# blackfin_d_codec.net
KiCad netlist of a schematic drawn in Altium Designer
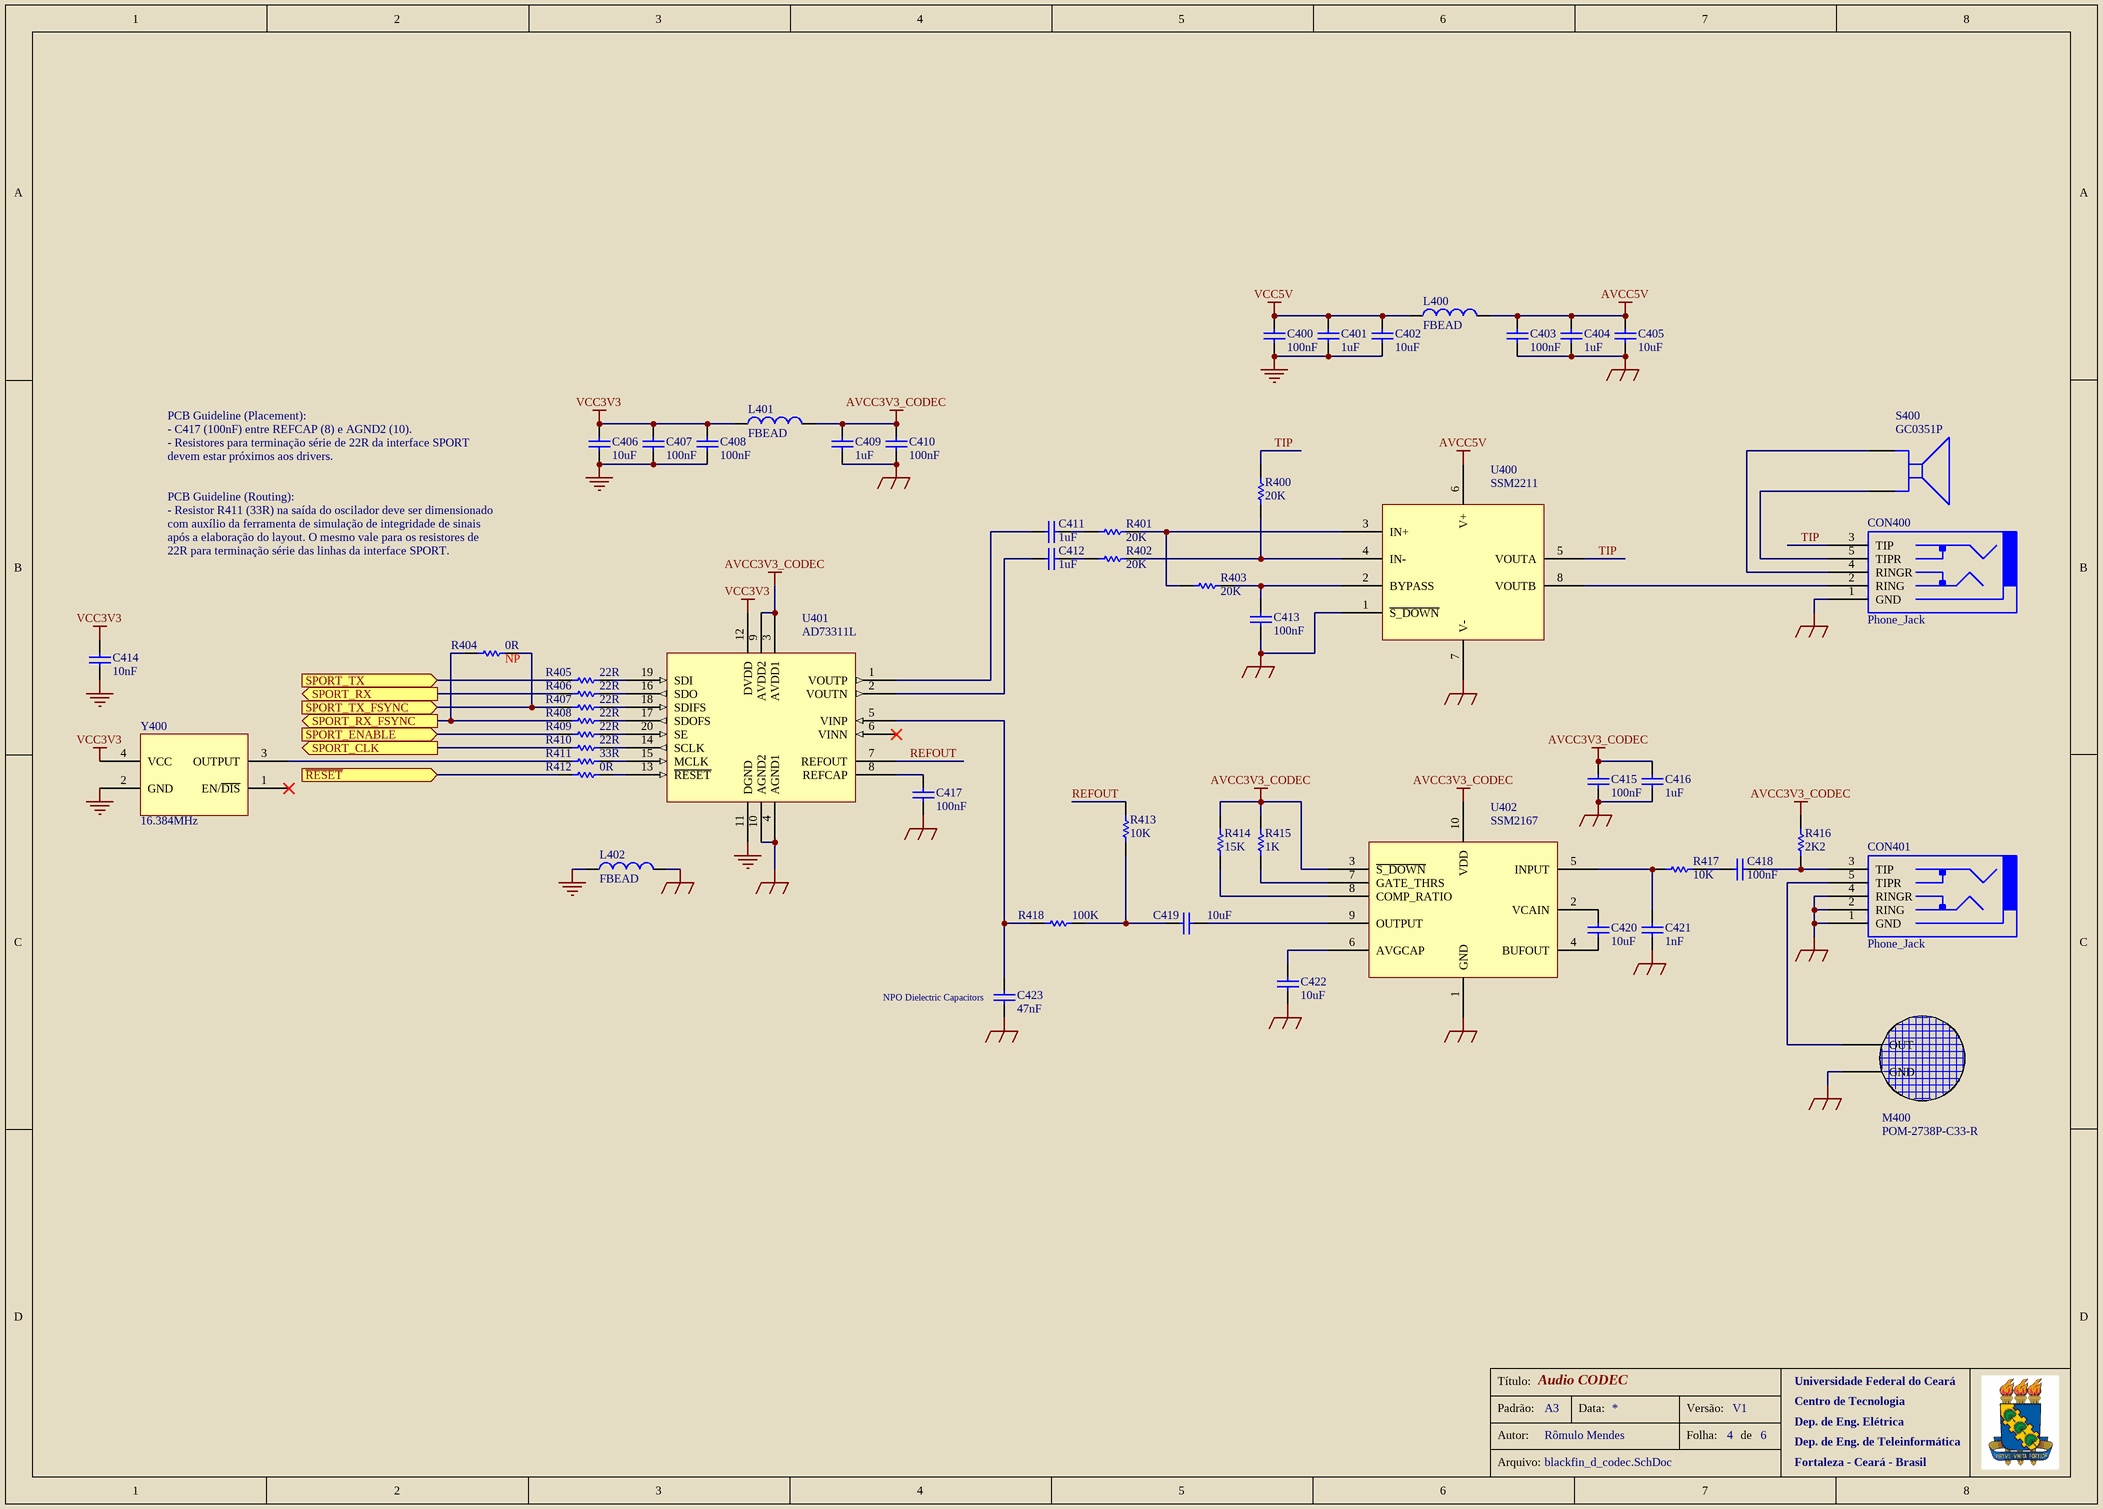
[diagram p0: blackfin_d_codec.SchDoc]

(export (version "E")
  (design (tool "Eeschema 10.0.6"))
  (components
    (comp (ref "C400")
      (value "100nF")
      (footprint "blackfin_pcblib:C_0603")
      (fields
        (field (name "EVENDORPART#") "81-GRM188R71E104KA01")
        (field (name "MANUFACTURER") "Murata")
        (field (name "PART#") "GRM188R71E104KA01J")
      )
      (libsource (lib "blackfin_schlib") (part "Capacitor"))
    )
    (comp (ref "C401")
      (value "1uF")
      (footprint "blackfin_pcblib:C_0603")
      (fields
        (field (name "EVENDORPART#") "81-GRM188F51E105ZA12")
        (field (name "MANUFACTURER") "Murata")
        (field (name "PART#") "GRM188F51E105ZA12D")
      )
      (libsource (lib "blackfin_schlib") (part "Capacitor"))
    )
    (comp (ref "C402")
      (value "10uF")
      (footprint "blackfin_pcblib:C_0805")
      (fields
        (field (name "EVENDORPART#") "810-C2012Y5V1C106Z")
        (field (name "MANUFACTURER") "TDK")
        (field (name "PART#") "C2012Y5V1C106Z")
      )
      (libsource (lib "blackfin_schlib") (part "Capacitor"))
    )
    (comp (ref "C403")
      (value "100nF")
      (footprint "blackfin_pcblib:C_0603")
      (fields
        (field (name "EVENDORPART#") "81-GRM188R71E104KA01")
        (field (name "MANUFACTURER") "Murata")
        (field (name "PART#") "GRM188R71E104KA01J")
      )
      (libsource (lib "blackfin_schlib") (part "Capacitor"))
    )
    (comp (ref "C404")
      (value "1uF")
      (footprint "blackfin_pcblib:C_0603")
      (fields
        (field (name "EVENDORPART#") "81-GRM188F51E105ZA12")
        (field (name "MANUFACTURER") "Murata")
        (field (name "PART#") "GRM188F51E105ZA12D")
      )
      (libsource (lib "blackfin_schlib") (part "Capacitor"))
    )
    (comp (ref "C405")
      (value "10uF")
      (footprint "blackfin_pcblib:C_0805")
      (fields
        (field (name "EVENDORPART#") "810-C2012Y5V1C106Z")
        (field (name "MANUFACTURER") "TDK")
        (field (name "PART#") "C2012Y5V1C106Z")
      )
      (libsource (lib "blackfin_schlib") (part "Capacitor"))
    )
    (comp (ref "C406")
      (value "10uF")
      (footprint "blackfin_pcblib:C_0805")
      (fields
        (field (name "EVENDORPART#") "810-C2012Y5V1C106Z")
        (field (name "MANUFACTURER") "TDK")
        (field (name "PART#") "C2012Y5V1C106Z")
      )
      (libsource (lib "blackfin_schlib") (part "Capacitor"))
    )
    (comp (ref "C407")
      (value "100nF")
      (footprint "blackfin_pcblib:C_0603")
      (fields
        (field (name "EVENDORPART#") "81-GRM188R71E104KA01")
        (field (name "MANUFACTURER") "Murata")
        (field (name "PART#") "GRM188R71E104KA01J")
      )
      (libsource (lib "blackfin_schlib") (part "Capacitor"))
    )
    (comp (ref "C408")
      (value "100nF")
      (footprint "blackfin_pcblib:C_0603")
      (fields
        (field (name "EVENDORPART#") "81-GRM188R71E104KA01")
        (field (name "MANUFACTURER") "Murata")
        (field (name "PART#") "GRM188R71E104KA01J")
      )
      (libsource (lib "blackfin_schlib") (part "Capacitor"))
    )
    (comp (ref "C409")
      (value "1uF")
      (footprint "blackfin_pcblib:C_0603")
      (fields
        (field (name "EVENDORPART#") "81-GRM188F51E105ZA12")
        (field (name "MANUFACTURER") "Murata")
        (field (name "PART#") "GRM188F51E105ZA12D")
      )
      (libsource (lib "blackfin_schlib") (part "Capacitor"))
    )
    (comp (ref "C410")
      (value "100nF")
      (footprint "blackfin_pcblib:C_0603")
      (fields
        (field (name "EVENDORPART#") "81-GRM188R71E104KA01")
        (field (name "MANUFACTURER") "Murata")
        (field (name "PART#") "GRM188R71E104KA01J")
      )
      (libsource (lib "blackfin_schlib") (part "Capacitor"))
    )
    (comp (ref "C411")
      (value "1uF")
      (footprint "blackfin_pcblib:C_0603")
      (fields
        (field (name "EVENDORPART#") "81-GRM188F51E105ZA12")
        (field (name "MANUFACTURER") "Murata")
        (field (name "PART#") "GRM188F51E105ZA12D")
      )
      (libsource (lib "blackfin_schlib") (part "Capacitor"))
    )
    (comp (ref "C412")
      (value "1uF")
      (footprint "blackfin_pcblib:C_0603")
      (fields
        (field (name "EVENDORPART#") "81-GRM188F51E105ZA12")
        (field (name "MANUFACTURER") "Murata")
        (field (name "PART#") "GRM188F51E105ZA12D")
      )
      (libsource (lib "blackfin_schlib") (part "Capacitor"))
    )
    (comp (ref "C413")
      (value "100nF")
      (footprint "blackfin_pcblib:C_0603")
      (fields
        (field (name "EVENDORPART#") "81-GRM188R71E104KA01")
        (field (name "MANUFACTURER") "Murata")
        (field (name "PART#") "GRM188R71E104KA01J")
      )
      (libsource (lib "blackfin_schlib") (part "Capacitor"))
    )
    (comp (ref "C414")
      (value "10nF")
      (footprint "blackfin_pcblib:C_0603")
      (fields
        (field (name "EVENDORPART#") "77-VJ0603Y103KXAPBC")
        (field (name "MANUFACTURER") "Vishay/Vitramon")
        (field (name "PART#") "VJ0603Y103KXAPW1BC")
      )
      (libsource (lib "blackfin_schlib") (part "Capacitor"))
    )
    (comp (ref "C415")
      (value "100nF")
      (footprint "blackfin_pcblib:C_0603")
      (fields
        (field (name "EVENDORPART#") "81-GRM188R71E104KA01")
        (field (name "MANUFACTURER") "Murata")
        (field (name "PART#") "GRM188R71E104KA01J")
      )
      (libsource (lib "blackfin_schlib") (part "Capacitor"))
    )
    (comp (ref "C416")
      (value "1uF")
      (footprint "blackfin_pcblib:C_0603")
      (fields
        (field (name "EVENDORPART#") "81-GRM188F51E105ZA12")
        (field (name "MANUFACTURER") "Murata")
        (field (name "PART#") "GRM188F51E105ZA12D")
      )
      (libsource (lib "blackfin_schlib") (part "Capacitor"))
    )
    (comp (ref "C417")
      (value "100nF")
      (footprint "blackfin_pcblib:C_0603")
      (fields
        (field (name "EVENDORPART#") "81-GRM188R71E104KA01")
        (field (name "MANUFACTURER") "Murata")
        (field (name "PART#") "GRM188R71E104KA01J")
      )
      (libsource (lib "blackfin_schlib") (part "Capacitor"))
    )
    (comp (ref "C418")
      (value "100nF")
      (footprint "blackfin_pcblib:C_0603")
      (fields
        (field (name "EVENDORPART#") "81-GRM188R71E104KA01")
        (field (name "MANUFACTURER") "Murata")
        (field (name "PART#") "GRM188R71E104KA01J")
      )
      (libsource (lib "blackfin_schlib") (part "Capacitor"))
    )
    (comp (ref "C419")
      (value "10uF")
      (footprint "blackfin_pcblib:C_0805")
      (fields
        (field (name "EVENDORPART#") "810-C2012Y5V1C106Z")
        (field (name "MANUFACTURER") "TDK")
        (field (name "PART#") "C2012Y5V1C106Z")
      )
      (libsource (lib "blackfin_schlib") (part "Capacitor"))
    )
    (comp (ref "C420")
      (value "10uF")
      (footprint "blackfin_pcblib:C_0805")
      (fields
        (field (name "EVENDORPART#") "810-C2012Y5V1C106Z")
        (field (name "MANUFACTURER") "TDK")
        (field (name "PART#") "C2012Y5V1C106Z")
      )
      (libsource (lib "blackfin_schlib") (part "Capacitor"))
    )
    (comp (ref "C421")
      (value "1nF")
      (footprint "blackfin_pcblib:C_0603")
      (fields
        (field (name "EVENDORPART#") "81-GRM1885C2A102JA01")
        (field (name "MANUFACTURER") "Murata")
        (field (name "PART#") "GRM1885C2A102JA01D")
      )
      (libsource (lib "blackfin_schlib") (part "Capacitor"))
    )
    (comp (ref "C422")
      (value "10uF")
      (footprint "blackfin_pcblib:C_0805")
      (fields
        (field (name "EVENDORPART#") "810-C2012Y5V1C106Z")
        (field (name "MANUFACTURER") "TDK")
        (field (name "PART#") "C2012Y5V1C106Z")
      )
      (libsource (lib "blackfin_schlib") (part "Capacitor"))
    )
    (comp (ref "C423")
      (value "47nF")
      (footprint "blackfin_pcblib:C_0603")
      (fields
        (field (name "EVENDORPART#") "81-GRM188R71H473KA61")
        (field (name "MANUFACTURER") "Murata")
        (field (name "PART#") "GRM188R71H473KA61D")
      )
      (libsource (lib "blackfin_schlib") (part "Capacitor"))
    )
    (comp (ref "CON400")
      (value "Phone_Jack")
      (footprint "blackfin_pcblib:Phone_Jack")
      (fields
        (field (name "EVENDORPART#") "CP1-2535SJCT-ND")
        (field (name "MANUFACTURER") "CUI Inc")
        (field (name "PART#") "SJ1-2535-SMT")
      )
      (libsource (lib "blackfin_schlib") (part "Phone_Jack"))
    )
    (comp (ref "CON401")
      (value "Phone_Jack")
      (footprint "blackfin_pcblib:Phone_Jack")
      (fields
        (field (name "EVENDORPART#") "CP1-2535SJCT-ND")
        (field (name "MANUFACTURER") "CUI Inc")
        (field (name "PART#") "SJ1-2535-SMT")
      )
      (libsource (lib "blackfin_schlib") (part "Phone_Jack"))
    )
    (comp (ref "L400")
      (value "FBEAD")
      (footprint "blackfin_pcblib:L_0603")
      (fields
        (field (name "EVENDORPART#") "875-MI0603L301R-10")
        (field (name "MANUFACTURER") "Laird Technologies")
        (field (name "PART#") "MI0603L301R-10")
      )
      (libsource (lib "blackfin_schlib") (part "Inductor"))
    )
    (comp (ref "L401")
      (value "FBEAD")
      (footprint "blackfin_pcblib:L_0603")
      (fields
        (field (name "EVENDORPART#") "875-MI0603L301R-10")
        (field (name "MANUFACTURER") "Laird Technologies")
        (field (name "PART#") "MI0603L301R-10")
      )
      (libsource (lib "blackfin_schlib") (part "Inductor"))
    )
    (comp (ref "L402")
      (value "FBEAD")
      (footprint "blackfin_pcblib:L_0603")
      (fields
        (field (name "EVENDORPART#") "875-MI0603L301R-10")
        (field (name "MANUFACTURER") "Laird Technologies")
        (field (name "PART#") "MI0603L301R-10")
      )
      (libsource (lib "blackfin_schlib") (part "Inductor"))
    )
    (comp (ref "M400")
      (value "POM-2738P-C33-R")
      (footprint "blackfin_pcblib:Microphone")
      (fields (field (name "EVENDORPART#") "665-POM2738PC33R") (field (name "MANUFACTURER") "PUI Audio"))
      (libsource (lib "blackfin_schlib") (part "Microphone"))
    )
    (comp (ref "R400")
      (value "20K")
      (footprint "blackfin_pcblib:R_0603")
      (fields
        (field (name "EVENDORPART#") "71-CRCW0603J-20K-E3")
        (field (name "PART#") "CRCW060320K0JNEA")
        (field (name "MANUFACTURER") "Vishay/Dale")
      )
      (libsource (lib "blackfin_schlib") (part "Resistor"))
    )
    (comp (ref "R401")
      (value "20K")
      (footprint "blackfin_pcblib:R_0603")
      (fields
        (field (name "EVENDORPART#") "71-CRCW0603J-20K-E3")
        (field (name "PART#") "CRCW060320K0JNEA")
        (field (name "MANUFACTURER") "Vishay/Dale")
      )
      (libsource (lib "blackfin_schlib") (part "Resistor"))
    )
    (comp (ref "R402")
      (value "20K")
      (footprint "blackfin_pcblib:R_0603")
      (fields
        (field (name "EVENDORPART#") "71-CRCW0603J-20K-E3")
        (field (name "PART#") "CRCW060320K0JNEA")
        (field (name "MANUFACTURER") "Vishay/Dale")
      )
      (libsource (lib "blackfin_schlib") (part "Resistor"))
    )
    (comp (ref "R403")
      (value "20K")
      (footprint "blackfin_pcblib:R_0603")
      (fields
        (field (name "EVENDORPART#") "71-CRCW0603J-20K-E3")
        (field (name "PART#") "CRCW060320K0JNEA")
        (field (name "MANUFACTURER") "Vishay/Dale")
      )
      (libsource (lib "blackfin_schlib") (part "Resistor"))
    )
    (comp (ref "R404")
      (value "0R")
      (footprint "blackfin_pcblib:R_0603")
      (fields
        (field (name "EVENDORPART#") "71-CRCW06030000Z0EB")
        (field (name "PART#") "CRCW06030000Z0EB")
        (field (name "MANUFACTURER") "Vishay/Dale")
      )
      (libsource (lib "blackfin_schlib") (part "Resistor"))
    )
    (comp (ref "R405")
      (value "22R")
      (footprint "blackfin_pcblib:R_0402")
      (fields
        (field (name "EVENDORPART#") "71-CRCW0402J-22-E3")
        (field (name "PART#") "CRCW040222R0JNED")
        (field (name "MANUFACTURER") "Vishay/Dale")
      )
      (libsource (lib "blackfin_schlib") (part "Resistor"))
    )
    (comp (ref "R406")
      (value "22R")
      (footprint "blackfin_pcblib:R_0402")
      (fields
        (field (name "EVENDORPART#") "71-CRCW0402J-22-E3")
        (field (name "PART#") "CRCW040222R0JNED")
        (field (name "MANUFACTURER") "Vishay/Dale")
      )
      (libsource (lib "blackfin_schlib") (part "Resistor"))
    )
    (comp (ref "R407")
      (value "22R")
      (footprint "blackfin_pcblib:R_0402")
      (fields
        (field (name "EVENDORPART#") "71-CRCW0402J-22-E3")
        (field (name "PART#") "CRCW040222R0JNED")
        (field (name "MANUFACTURER") "Vishay/Dale")
      )
      (libsource (lib "blackfin_schlib") (part "Resistor"))
    )
    (comp (ref "R408")
      (value "22R")
      (footprint "blackfin_pcblib:R_0402")
      (fields
        (field (name "EVENDORPART#") "71-CRCW0402J-22-E3")
        (field (name "PART#") "CRCW040222R0JNED")
        (field (name "MANUFACTURER") "Vishay/Dale")
      )
      (libsource (lib "blackfin_schlib") (part "Resistor"))
    )
    (comp (ref "R409")
      (value "22R")
      (footprint "blackfin_pcblib:R_0402")
      (fields
        (field (name "EVENDORPART#") "71-CRCW0402J-22-E3")
        (field (name "PART#") "CRCW040222R0JNED")
        (field (name "MANUFACTURER") "Vishay/Dale")
      )
      (libsource (lib "blackfin_schlib") (part "Resistor"))
    )
    (comp (ref "R410")
      (value "22R")
      (footprint "blackfin_pcblib:R_0402")
      (fields
        (field (name "EVENDORPART#") "71-CRCW0402J-22-E3")
        (field (name "PART#") "CRCW040222R0JNED")
        (field (name "MANUFACTURER") "Vishay/Dale")
      )
      (libsource (lib "blackfin_schlib") (part "Resistor"))
    )
    (comp (ref "R411")
      (value "33R")
      (footprint "blackfin_pcblib:R_0402")
      (fields
        (field (name "EVENDORPART#") "71-CRCW0402J-33-E3")
        (field (name "PART#") "CRCW040233R0JNED")
        (field (name "MANUFACTURER") "Vishay/Dale")
      )
      (libsource (lib "blackfin_schlib") (part "Resistor"))
    )
    (comp (ref "R412")
      (value "0R")
      (footprint "blackfin_pcblib:R_0603")
      (fields
        (field (name "EVENDORPART#") "71-CRCW06030000Z0EB")
        (field (name "PART#") "CRCW06030000Z0EB")
        (field (name "MANUFACTURER") "Vishay/Dale")
      )
      (libsource (lib "blackfin_schlib") (part "Resistor"))
    )
    (comp (ref "R413")
      (value "10K")
      (footprint "blackfin_pcblib:R_0603")
      (fields
        (field (name "EVENDORPART#") "71-CRCW0603-10K-E3")
        (field (name "PART#") "CRCW060310K0FKEA")
        (field (name "MANUFACTURER") "Vishay/Dale")
      )
      (libsource (lib "blackfin_schlib") (part "Resistor"))
    )
    (comp (ref "R414")
      (value "15K")
      (footprint "blackfin_pcblib:R_0603")
      (fields
        (field (name "EVENDORPART#") "71-CRCW0603J-15K-E3")
        (field (name "PART#") "CRCW060315K0JNEA")
        (field (name "MANUFACTURER") "Vishay/Dale")
      )
      (libsource (lib "blackfin_schlib") (part "Resistor"))
    )
    (comp (ref "R415")
      (value "1K")
      (footprint "blackfin_pcblib:R_0603")
      (fields
        (field (name "EVENDORPART#") "71-CRCW06031K00JNEB")
        (field (name "PART#") "CRCW06031K00JNEB")
        (field (name "MANUFACTURER") "Vishay/Dale")
      )
      (libsource (lib "blackfin_schlib") (part "Resistor"))
    )
    (comp (ref "R416")
      (value "2K2")
      (footprint "blackfin_pcblib:R_0603")
      (fields
        (field (name "EVENDORPART#") "71-CRCW06032K20JNEB")
        (field (name "PART#") "CRCW06032K20JNEB")
        (field (name "MANUFACTURER") "Vishay/Dale")
      )
      (libsource (lib "blackfin_schlib") (part "Resistor"))
    )
    (comp (ref "R417")
      (value "10K")
      (footprint "blackfin_pcblib:R_0603")
      (fields
        (field (name "EVENDORPART#") "71-CRCW0603-10K-E3")
        (field (name "PART#") "CRCW060310K0FKEA")
        (field (name "MANUFACTURER") "Vishay/Dale")
      )
      (libsource (lib "blackfin_schlib") (part "Resistor"))
    )
    (comp (ref "R418")
      (value "100K")
      (footprint "blackfin_pcblib:R_0603")
      (fields
        (field (name "EVENDORPART#") "71-CRCW0603J-100K-E3")
        (field (name "PART#") "CRCW0603100KJNEA")
        (field (name "MANUFACTURER") "Vishay/Dale")
      )
      (libsource (lib "blackfin_schlib") (part "Resistor"))
    )
    (comp (ref "S400")
      (value "GC0351P")
      (footprint "blackfin_pcblib:Speaker")
      (fields
        (field (name "EVENDORPART#") "GC0351P-3-ND")
        (field (name "PART#") "GC0351P-3")
        (field (name "MANUFACTURER") "CUI Inc")
      )
      (libsource (lib "blackfin_schlib") (part "Speaker"))
    )
    (comp (ref "U400")
      (value "SSM2211")
      (footprint "blackfin_pcblib:SOIC-8 (SSM2211)")
      (fields
        (field (name "EVENDORPART#") "SSM2211SZ-ND")
        (field (name "PART#") "SSM2211SZ")
        (field (name "MANUFACTURER") "Analog Devices")
      )
      (libsource (lib "blackfin_schlib") (part "SSM2211"))
    )
    (comp (ref "U401")
      (value "AD73311L")
      (footprint "blackfin_pcblib:TSSOP-20")
      (fields (field (name "EVENDORPART#") "AD73311LARUZ") (field (name "MANUFACTURER") "Analog Devices"))
      (libsource (lib "blackfin_schlib") (part "AD73311L"))
    )
    (comp (ref "U402")
      (value "SSM2167")
      (footprint "blackfin_pcblib:MSOP-10")
      (fields
        (field (name "EVENDORPART#") "SSM2167-1RMZ-REELCT-ND")
        (field (name "MANUFACTURER") "Analog Devices")
        (field (name "PART#") "SSM2167-1RMZ-REEL")
      )
      (libsource (lib "blackfin_schlib") (part "SSM2167"))
    )
    (comp (ref "Y400")
      (value "16.384MHz")
      (footprint "blackfin_pcblib:OSC_16.384MHz")
      (fields
        (field (name "EVENDORPART#") "695-CSX750FBC-163")
        (field (name "PART#") "CSX750FBC-16.384M-UT")
        (field (name "MANUFACTURER") "Citizen")
      )
      (libsource (lib "blackfin_schlib") (part "Oscillator_16.384MHz"))
    )
  )
  (nets
    (net (code "1") (name "/REFOUT") (class "Default")
      (node (ref "R413") (pin "2") (pinfunction "2_2") (pintype "passive"))
      (node (ref "U401") (pin "7") (pinfunction "REFOUT_7") (pintype "power_in"))
    )
    (net (code "2") (name "/SPORT_CLK") (class "Default")
      (node (ref "R410") (pin "1") (pinfunction "1_1") (pintype "passive"))
    )
    (net (code "3") (name "/SPORT_ENABLE") (class "Default")
      (node (ref "R409") (pin "1") (pinfunction "1_1") (pintype "passive"))
    )
    (net (code "4") (name "/SPORT_RX") (class "Default")
      (node (ref "R406") (pin "1") (pinfunction "1_1") (pintype "passive"))
    )
    (net (code "5") (name "/SPORT_RX_FSYNC") (class "Default")
      (node (ref "R404") (pin "1") (pinfunction "1_1") (pintype "passive"))
      (node (ref "R408") (pin "1") (pinfunction "1_1") (pintype "passive"))
    )
    (net (code "6") (name "/SPORT_TX") (class "Default")
      (node (ref "R405") (pin "1") (pinfunction "1_1") (pintype "passive"))
    )
    (net (code "7") (name "/SPORT_TX_FSYNC") (class "Default")
      (node (ref "R404") (pin "2") (pinfunction "2_2") (pintype "passive"))
      (node (ref "R407") (pin "1") (pinfunction "1_1") (pintype "passive"))
    )
    (net (code "8") (name "/TIP") (class "Default")
      (node (ref "CON400") (pin "3") (pinfunction "TIP_3") (pintype "passive"))
      (node (ref "R400") (pin "2") (pinfunction "2_2") (pintype "passive"))
      (node (ref "U400") (pin "5") (pinfunction "VOUTA_5") (pintype "passive"))
    )
    (net (code "9") (name "/~{RESET}") (class "Default")
      (node (ref "R412") (pin "1") (pinfunction "1_1") (pintype "passive"))
    )
    (net (code "10") (name "AVCC3V3_CODEC") (class "Default")
      (node (ref "C409") (pin "2") (pinfunction "2_2") (pintype "passive"))
      (node (ref "C410") (pin "2") (pinfunction "2_2") (pintype "passive"))
      (node (ref "C415") (pin "2") (pinfunction "2_2") (pintype "passive"))
      (node (ref "C416") (pin "2") (pinfunction "2_2") (pintype "passive"))
      (node (ref "L401") (pin "2") (pinfunction "2_2") (pintype "passive"))
      (node (ref "R414") (pin "2") (pinfunction "2_2") (pintype "passive"))
      (node (ref "R415") (pin "2") (pinfunction "2_2") (pintype "passive"))
      (node (ref "R416") (pin "1") (pinfunction "1_1") (pintype "passive"))
      (node (ref "U401") (pin "3") (pinfunction "AVDD1_3") (pintype "power_in"))
      (node (ref "U401") (pin "9") (pinfunction "AVDD2_9") (pintype "power_in"))
      (node (ref "U402") (pin "10") (pinfunction "VDD_10") (pintype "passive"))
      (node (ref "U402") (pin "3") (pinfunction "~{S_DOWN}_3") (pintype "passive"))
    )
    (net (code "11") (name "AVCC5V") (class "Default")
      (node (ref "C403") (pin "2") (pinfunction "2_2") (pintype "passive"))
      (node (ref "C404") (pin "2") (pinfunction "2_2") (pintype "passive"))
      (node (ref "C405") (pin "2") (pinfunction "2_2") (pintype "passive"))
      (node (ref "L400") (pin "2") (pinfunction "2_2") (pintype "passive"))
      (node (ref "U400") (pin "6") (pinfunction "V+_6") (pintype "passive"))
    )
    (net (code "12") (name "EARTH") (class "Default")
      (node (ref "C403") (pin "1") (pinfunction "1_1") (pintype "passive"))
      (node (ref "C404") (pin "1") (pinfunction "1_1") (pintype "passive"))
      (node (ref "C405") (pin "1") (pinfunction "1_1") (pintype "passive"))
      (node (ref "C409") (pin "1") (pinfunction "1_1") (pintype "passive"))
      (node (ref "C410") (pin "1") (pinfunction "1_1") (pintype "passive"))
      (node (ref "C413") (pin "1") (pinfunction "1_1") (pintype "passive"))
      (node (ref "C415") (pin "1") (pinfunction "1_1") (pintype "passive"))
      (node (ref "C416") (pin "1") (pinfunction "1_1") (pintype "passive"))
      (node (ref "C417") (pin "1") (pinfunction "1_1") (pintype "passive"))
      (node (ref "C421") (pin "1") (pinfunction "1_1") (pintype "passive"))
      (node (ref "C422") (pin "2") (pinfunction "2_2") (pintype "passive"))
      (node (ref "C423") (pin "1") (pinfunction "1_1") (pintype "passive"))
      (node (ref "CON400") (pin "1") (pinfunction "GND_1") (pintype "passive"))
      (node (ref "CON401") (pin "1") (pinfunction "GND_1") (pintype "passive"))
      (node (ref "CON401") (pin "2") (pinfunction "RING_2") (pintype "passive"))
      (node (ref "CON401") (pin "4") (pinfunction "RINGR_4") (pintype "passive"))
      (node (ref "L402") (pin "2") (pinfunction "2_2") (pintype "passive"))
      (node (ref "M400") (pin "2") (pinfunction "GND_2") (pintype "passive"))
      (node (ref "U400") (pin "1") (pinfunction "~{S_DOWN}_1") (pintype "passive"))
      (node (ref "U400") (pin "7") (pinfunction "V-_7") (pintype "passive"))
      (node (ref "U401") (pin "10") (pinfunction "AGND2_10") (pintype "power_in"))
      (node (ref "U401") (pin "4") (pinfunction "AGND1_4") (pintype "power_in"))
      (node (ref "U402") (pin "1") (pinfunction "GND_1") (pintype "passive"))
    )
    (net (code "13") (name "GND") (class "Default")
      (node (ref "C400") (pin "1") (pinfunction "1_1") (pintype "passive"))
      (node (ref "C401") (pin "1") (pinfunction "1_1") (pintype "passive"))
      (node (ref "C402") (pin "1") (pinfunction "1_1") (pintype "passive"))
      (node (ref "C406") (pin "1") (pinfunction "1_1") (pintype "passive"))
      (node (ref "C407") (pin "1") (pinfunction "1_1") (pintype "passive"))
      (node (ref "C408") (pin "1") (pinfunction "1_1") (pintype "passive"))
      (node (ref "C414") (pin "1") (pinfunction "1_1") (pintype "passive"))
      (node (ref "L402") (pin "1") (pinfunction "1_1") (pintype "passive"))
      (node (ref "U401") (pin "11") (pinfunction "DGND_11") (pintype "power_in"))
      (node (ref "Y400") (pin "2") (pinfunction "GND_2") (pintype "passive"))
    )
    (net (code "14") (name "Net-(C411-Pad1)") (class "Default")
      (node (ref "C411") (pin "1") (pinfunction "1_1") (pintype "passive"))
      (node (ref "R401") (pin "2") (pinfunction "2_2") (pintype "passive"))
    )
    (net (code "15") (name "Net-(C412-Pad1)") (class "Default")
      (node (ref "C412") (pin "1") (pinfunction "1_1") (pintype "passive"))
      (node (ref "R402") (pin "2") (pinfunction "2_2") (pintype "passive"))
    )
    (net (code "16") (name "Net-(C418-Pad2)") (class "Default")
      (node (ref "C418") (pin "2") (pinfunction "2_2") (pintype "passive"))
      (node (ref "R417") (pin "1") (pinfunction "1_1") (pintype "passive"))
    )
    (net (code "17") (name "Net-(C419-Pad2)") (class "Default")
      (node (ref "C419") (pin "2") (pinfunction "2_2") (pintype "passive"))
      (node (ref "R413") (pin "1") (pinfunction "1_1") (pintype "passive"))
      (node (ref "R418") (pin "1") (pinfunction "1_1") (pintype "passive"))
    )
    (net (code "18") (name "Net-(CON400-RING)") (class "Default")
      (node (ref "CON400") (pin "2") (pinfunction "RING_2") (pintype "passive"))
      (node (ref "U400") (pin "8") (pinfunction "VOUTB_8") (pintype "passive"))
    )
    (net (code "19") (name "Net-(CON400-RINGR)") (class "Default")
      (node (ref "CON400") (pin "4") (pinfunction "RINGR_4") (pintype "passive"))
      (node (ref "S400") (pin "1") (pinfunction "CKT1_1") (pintype "passive"))
    )
    (net (code "20") (name "Net-(CON400-TIPR)") (class "Default")
      (node (ref "CON400") (pin "5") (pinfunction "TIPR_5") (pintype "passive"))
      (node (ref "S400") (pin "2") (pinfunction "CKT2_2") (pintype "passive"))
    )
    (net (code "21") (name "Net-(CON401-TIP)") (class "Default")
      (node (ref "C418") (pin "1") (pinfunction "1_1") (pintype "passive"))
      (node (ref "CON401") (pin "3") (pinfunction "TIP_3") (pintype "passive"))
      (node (ref "R416") (pin "2") (pinfunction "2_2") (pintype "passive"))
    )
    (net (code "22") (name "Net-(CON401-TIPR)") (class "Default")
      (node (ref "CON401") (pin "5") (pinfunction "TIPR_5") (pintype "passive"))
      (node (ref "M400") (pin "1") (pinfunction "OUT_1") (pintype "passive"))
    )
    (net (code "23") (name "Net-(U400-BYPASS)") (class "Default")
      (node (ref "C413") (pin "2") (pinfunction "2_2") (pintype "passive"))
      (node (ref "R403") (pin "1") (pinfunction "1_1") (pintype "passive"))
      (node (ref "U400") (pin "2") (pinfunction "BYPASS_2") (pintype "passive"))
    )
    (net (code "24") (name "Net-(U400-IN+)") (class "Default")
      (node (ref "R401") (pin "1") (pinfunction "1_1") (pintype "passive"))
      (node (ref "R403") (pin "2") (pinfunction "2_2") (pintype "passive"))
      (node (ref "U400") (pin "3") (pinfunction "IN+_3") (pintype "passive"))
    )
    (net (code "25") (name "Net-(U400-IN-)") (class "Default")
      (node (ref "R400") (pin "1") (pinfunction "1_1") (pintype "passive"))
      (node (ref "R402") (pin "1") (pinfunction "1_1") (pintype "passive"))
      (node (ref "U400") (pin "4") (pinfunction "IN-_4") (pintype "passive"))
    )
    (net (code "26") (name "Net-(U401-MCLK)") (class "Default")
      (node (ref "R411") (pin "2") (pinfunction "2_2") (pintype "passive"))
      (node (ref "U401") (pin "15") (pinfunction "MCLK_15") (pintype "input"))
    )
    (net (code "27") (name "Net-(U401-REFCAP)") (class "Default")
      (node (ref "C417") (pin "2") (pinfunction "2_2") (pintype "passive"))
      (node (ref "U401") (pin "8") (pinfunction "REFCAP_8") (pintype "power_in"))
    )
    (net (code "28") (name "Net-(U401-SCLK)") (class "Default")
      (node (ref "R410") (pin "2") (pinfunction "2_2") (pintype "passive"))
      (node (ref "U401") (pin "14") (pinfunction "SCLK_14") (pintype "output"))
    )
    (net (code "29") (name "Net-(U401-SDI)") (class "Default")
      (node (ref "R405") (pin "2") (pinfunction "2_2") (pintype "passive"))
      (node (ref "U401") (pin "19") (pinfunction "SDI_19") (pintype "input"))
    )
    (net (code "30") (name "Net-(U401-SDIFS)") (class "Default")
      (node (ref "R407") (pin "2") (pinfunction "2_2") (pintype "passive"))
      (node (ref "U401") (pin "18") (pinfunction "SDIFS_18") (pintype "input"))
    )
    (net (code "31") (name "Net-(U401-SDO)") (class "Default")
      (node (ref "R406") (pin "2") (pinfunction "2_2") (pintype "passive"))
      (node (ref "U401") (pin "16") (pinfunction "SDO_16") (pintype "output"))
    )
    (net (code "32") (name "Net-(U401-SDOFS)") (class "Default")
      (node (ref "R408") (pin "2") (pinfunction "2_2") (pintype "passive"))
      (node (ref "U401") (pin "17") (pinfunction "SDOFS_17") (pintype "output"))
    )
    (net (code "33") (name "Net-(U401-SE)") (class "Default")
      (node (ref "R409") (pin "2") (pinfunction "2_2") (pintype "passive"))
      (node (ref "U401") (pin "20") (pinfunction "SE_20") (pintype "input"))
    )
    (net (code "34") (name "Net-(U401-VINP)") (class "Default")
      (node (ref "C423") (pin "2") (pinfunction "2_2") (pintype "passive"))
      (node (ref "R418") (pin "2") (pinfunction "2_2") (pintype "passive"))
      (node (ref "U401") (pin "5") (pinfunction "VINP_5") (pintype "input"))
    )
    (net (code "35") (name "Net-(U401-VOUTN)") (class "Default")
      (node (ref "C412") (pin "2") (pinfunction "2_2") (pintype "passive"))
      (node (ref "U401") (pin "2") (pinfunction "VOUTN_2") (pintype "output"))
    )
    (net (code "36") (name "Net-(U401-VOUTP)") (class "Default")
      (node (ref "C411") (pin "2") (pinfunction "2_2") (pintype "passive"))
      (node (ref "U401") (pin "1") (pinfunction "VOUTP_1") (pintype "output"))
    )
    (net (code "37") (name "Net-(U401-~{RESET})") (class "Default")
      (node (ref "R412") (pin "2") (pinfunction "2_2") (pintype "passive"))
      (node (ref "U401") (pin "13") (pinfunction "~{RESET}_13") (pintype "input"))
    )
    (net (code "38") (name "Net-(U402-AVGCAP)") (class "Default")
      (node (ref "C422") (pin "1") (pinfunction "1_1") (pintype "passive"))
      (node (ref "U402") (pin "6") (pinfunction "AVGCAP_6") (pintype "passive"))
    )
    (net (code "39") (name "Net-(U402-BUFOUT)") (class "Default")
      (node (ref "C420") (pin "1") (pinfunction "1_1") (pintype "passive"))
      (node (ref "U402") (pin "4") (pinfunction "BUFOUT_4") (pintype "passive"))
    )
    (net (code "40") (name "Net-(U402-COMP_RATIO)") (class "Default")
      (node (ref "R414") (pin "1") (pinfunction "1_1") (pintype "passive"))
      (node (ref "U402") (pin "8") (pinfunction "COMP_RATIO_8") (pintype "passive"))
    )
    (net (code "41") (name "Net-(U402-GATE_THRS)") (class "Default")
      (node (ref "R415") (pin "1") (pinfunction "1_1") (pintype "passive"))
      (node (ref "U402") (pin "7") (pinfunction "GATE_THRS_7") (pintype "passive"))
    )
    (net (code "42") (name "Net-(U402-INPUT)") (class "Default")
      (node (ref "C421") (pin "2") (pinfunction "2_2") (pintype "passive"))
      (node (ref "R417") (pin "2") (pinfunction "2_2") (pintype "passive"))
      (node (ref "U402") (pin "5") (pinfunction "INPUT_5") (pintype "passive"))
    )
    (net (code "43") (name "Net-(U402-OUTPUT)") (class "Default")
      (node (ref "C419") (pin "1") (pinfunction "1_1") (pintype "passive"))
      (node (ref "U402") (pin "9") (pinfunction "OUTPUT_9") (pintype "passive"))
    )
    (net (code "44") (name "Net-(U402-VCAIN)") (class "Default")
      (node (ref "C420") (pin "2") (pinfunction "2_2") (pintype "passive"))
      (node (ref "U402") (pin "2") (pinfunction "VCAIN_2") (pintype "passive"))
    )
    (net (code "45") (name "Net-(Y400-OUTPUT)") (class "Default")
      (node (ref "R411") (pin "1") (pinfunction "1_1") (pintype "passive"))
      (node (ref "Y400") (pin "3") (pinfunction "OUTPUT_3") (pintype "passive"))
    )
    (net (code "46") (name "VCC3V3") (class "Default")
      (node (ref "C406") (pin "2") (pinfunction "2_2") (pintype "passive"))
      (node (ref "C407") (pin "2") (pinfunction "2_2") (pintype "passive"))
      (node (ref "C408") (pin "2") (pinfunction "2_2") (pintype "passive"))
      (node (ref "C414") (pin "2") (pinfunction "2_2") (pintype "passive"))
      (node (ref "L401") (pin "1") (pinfunction "1_1") (pintype "passive"))
      (node (ref "U401") (pin "12") (pinfunction "DVDD_12") (pintype "power_in"))
      (node (ref "Y400") (pin "4") (pinfunction "VCC_4") (pintype "passive"))
    )
    (net (code "47") (name "VCC5V") (class "Default")
      (node (ref "C400") (pin "2") (pinfunction "2_2") (pintype "passive"))
      (node (ref "C401") (pin "2") (pinfunction "2_2") (pintype "passive"))
      (node (ref "C402") (pin "2") (pinfunction "2_2") (pintype "passive"))
      (node (ref "L400") (pin "1") (pinfunction "1_1") (pintype "passive"))
    )
    (net (code "48") (name "unconnected-(U401-VINN-Pad6)") (class "Default")
      (node (ref "U401") (pin "6") (pinfunction "VINN_6") (pintype "input+no_connect"))
    )
    (net (code "49") (name "unconnected-(Y400-EN{slash}~{DIS}-Pad1)") (class "Default")
      (node (ref "Y400") (pin "1") (pinfunction "EN/~{DIS}_1") (pintype "passive+no_connect"))
    )
  )
)
